# SPIDriverSRAM_v1.net
KiCad netlist of a schematic drawn in EAGLE
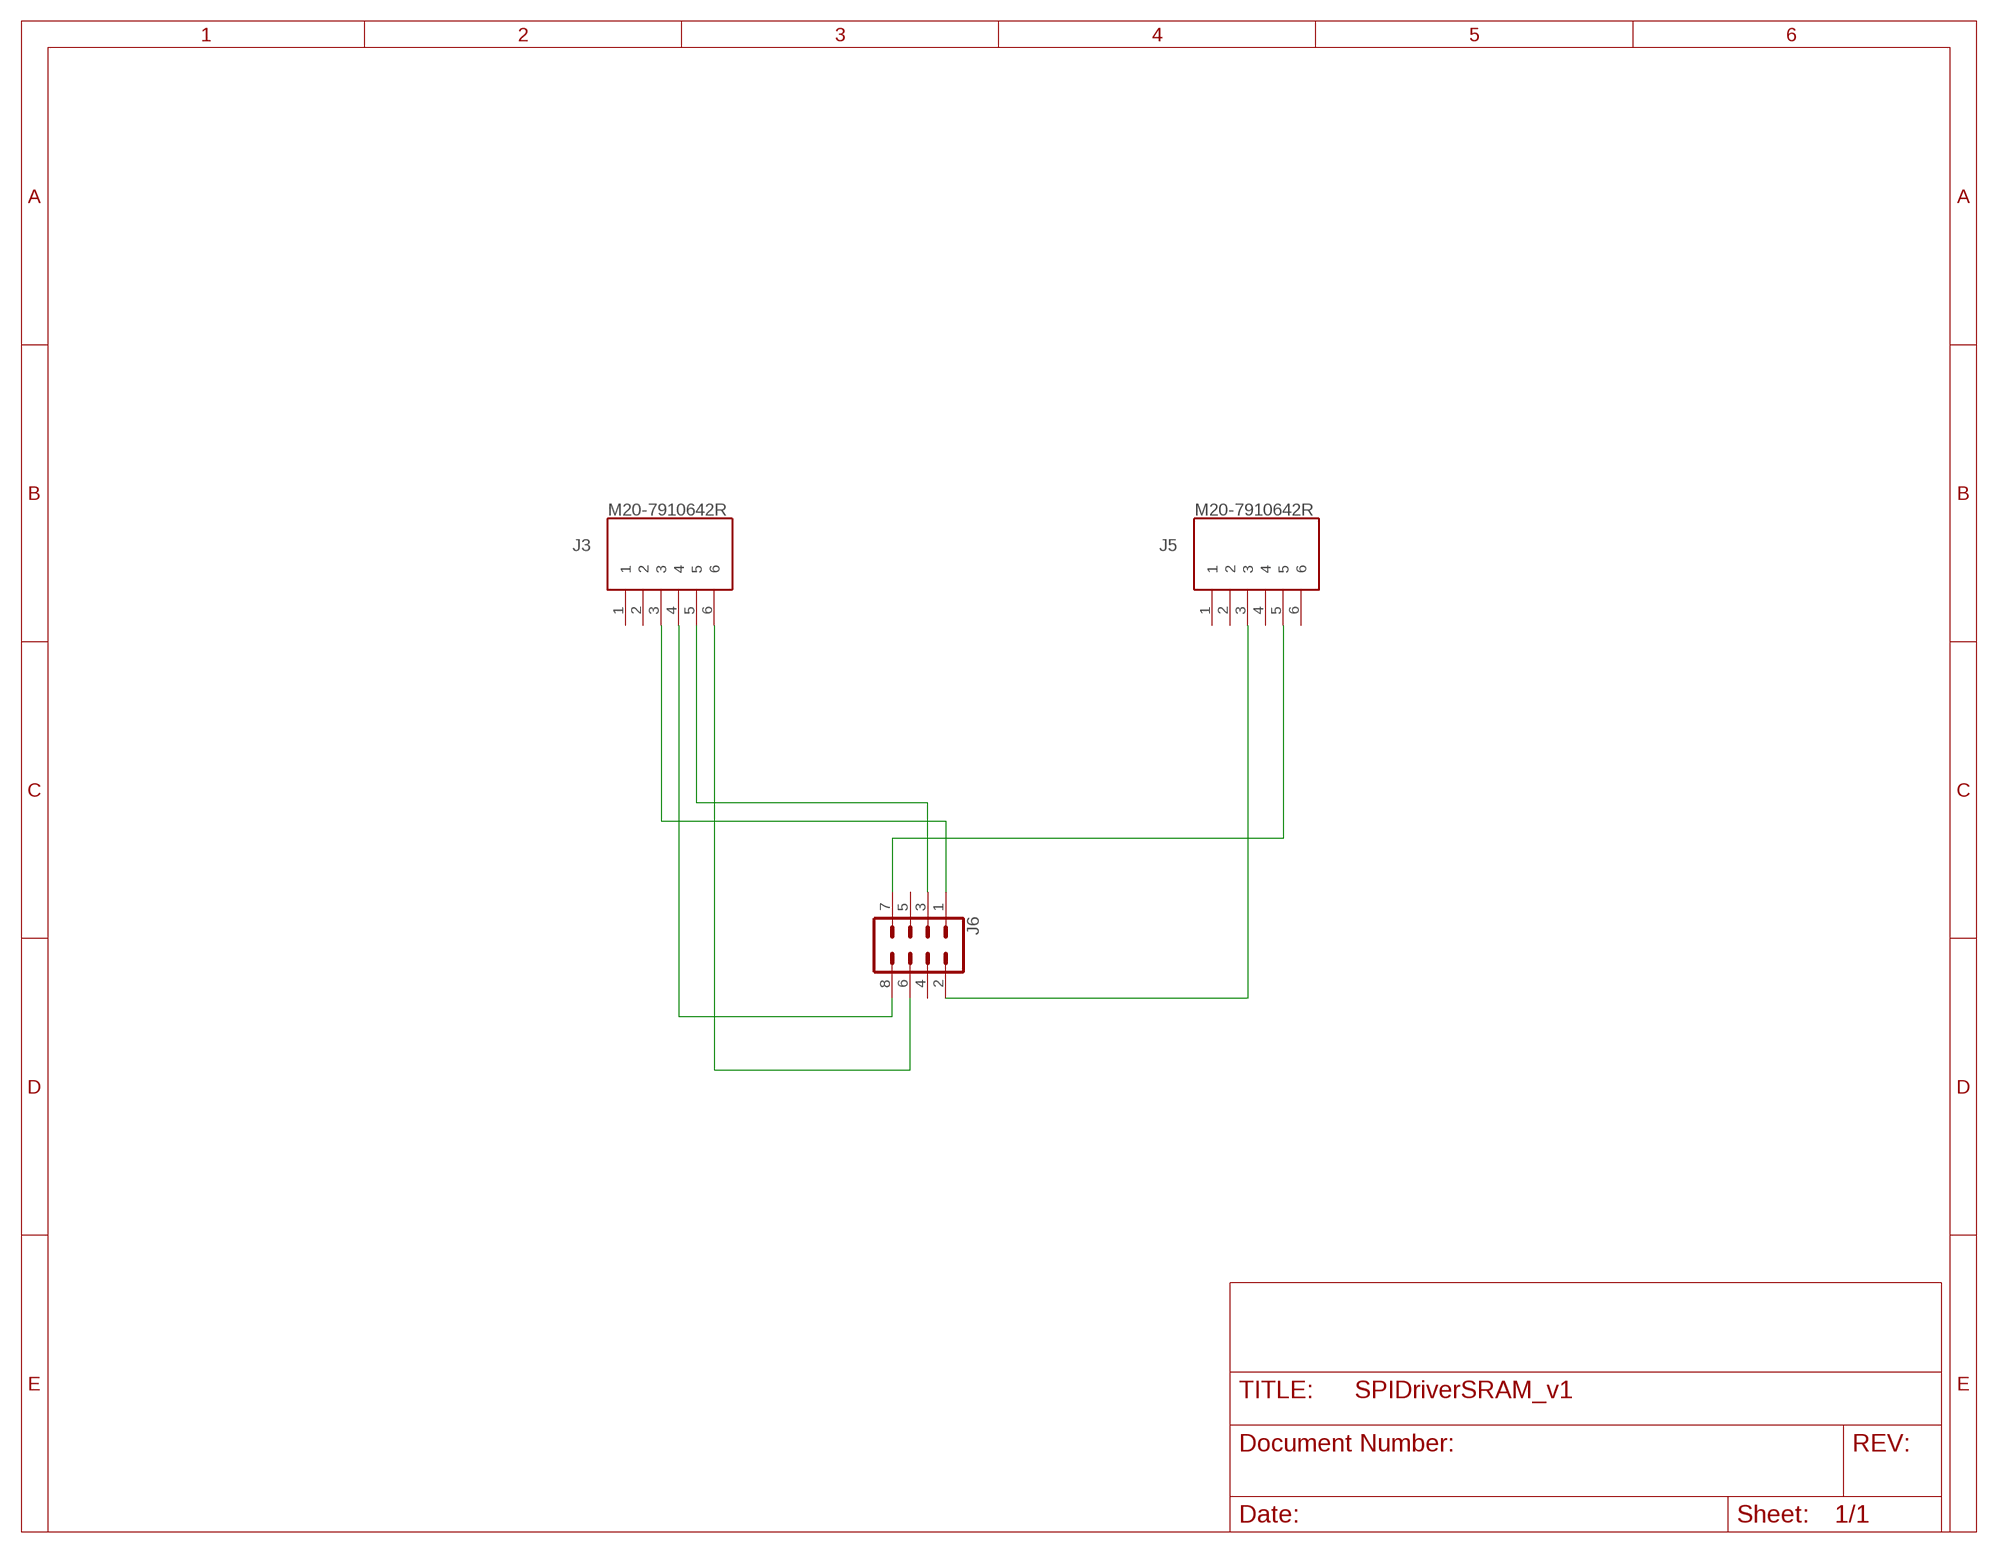
[diagram p0: schematic, sheet 1]

(export (version "E")
  (design (tool "Eeschema 10.0.6"))
  (components
    (comp (ref "J3")
      (value "M20-7910642R")
      (footprint "eagle-import:M20-7910642R")
      (fields (field (name "MOUSER_PART_NUMBER") "855-M20-7910642R"))
      (libsource (lib "eagle-import") (part "M20-7910642R"))
    )
    (comp (ref "J5")
      (value "M20-7910642R")
      (footprint "eagle-import:M20-7910642R")
      (fields (field (name "MOUSER_PART_NUMBER") "855-M20-7910642R"))
      (libsource (lib "eagle-import") (part "M20-7910642R"))
    )
    (comp (ref "J6")
      (value "CONN_04X2")
      (footprint "eagle-import:2X4")
      (libsource (lib "eagle-import") (part "CONN_04X2"))
    )
  )
  (nets
    (net (code "1") (name "Net-(J3-Pad3)") (class "Default")
      (node (ref "J3") (pin "3") (pinfunction "3_3") (pintype "bidirectional"))
      (node (ref "J6") (pin "1") (pinfunction "1_1") (pintype "passive"))
    )
    (net (code "2") (name "Net-(J3-Pad4)") (class "Default")
      (node (ref "J3") (pin "4") (pinfunction "4_4") (pintype "bidirectional"))
      (node (ref "J6") (pin "8") (pinfunction "8_8") (pintype "passive"))
    )
    (net (code "3") (name "Net-(J3-Pad5)") (class "Default")
      (node (ref "J3") (pin "5") (pinfunction "5_5") (pintype "bidirectional"))
      (node (ref "J6") (pin "3") (pinfunction "3_3") (pintype "passive"))
    )
    (net (code "4") (name "Net-(J3-Pad6)") (class "Default")
      (node (ref "J3") (pin "6") (pinfunction "6_6") (pintype "bidirectional"))
      (node (ref "J6") (pin "6") (pinfunction "6_6") (pintype "passive"))
    )
    (net (code "5") (name "Net-(J5-Pad3)") (class "Default")
      (node (ref "J5") (pin "3") (pinfunction "3_3") (pintype "bidirectional"))
      (node (ref "J6") (pin "2") (pinfunction "2_2") (pintype "passive"))
    )
    (net (code "6") (name "Net-(J5-Pad5)") (class "Default")
      (node (ref "J5") (pin "5") (pinfunction "5_5") (pintype "bidirectional"))
      (node (ref "J6") (pin "7") (pinfunction "7_7") (pintype "passive"))
    )
    (net (code "7") (name "unconnected-(J3-Pad1)") (class "Default")
      (node (ref "J3") (pin "1") (pinfunction "1_1") (pintype "bidirectional"))
    )
    (net (code "8") (name "unconnected-(J3-Pad2)") (class "Default")
      (node (ref "J3") (pin "2") (pinfunction "2_2") (pintype "bidirectional"))
    )
    (net (code "9") (name "unconnected-(J5-Pad1)") (class "Default")
      (node (ref "J5") (pin "1") (pinfunction "1_1") (pintype "bidirectional"))
    )
    (net (code "10") (name "unconnected-(J5-Pad2)") (class "Default")
      (node (ref "J5") (pin "2") (pinfunction "2_2") (pintype "bidirectional"))
    )
    (net (code "11") (name "unconnected-(J5-Pad4)") (class "Default")
      (node (ref "J5") (pin "4") (pinfunction "4_4") (pintype "bidirectional"))
    )
    (net (code "12") (name "unconnected-(J5-Pad6)") (class "Default")
      (node (ref "J5") (pin "6") (pinfunction "6_6") (pintype "bidirectional"))
    )
    (net (code "13") (name "unconnected-(J6-Pad4)") (class "Default")
      (node (ref "J6") (pin "4") (pinfunction "4_4") (pintype "passive"))
    )
    (net (code "14") (name "unconnected-(J6-Pad5)") (class "Default")
      (node (ref "J6") (pin "5") (pinfunction "5_5") (pintype "passive"))
    )
  )
)
